# LED_Indicator.net
KiCad netlist of a schematic drawn in Altium Designer
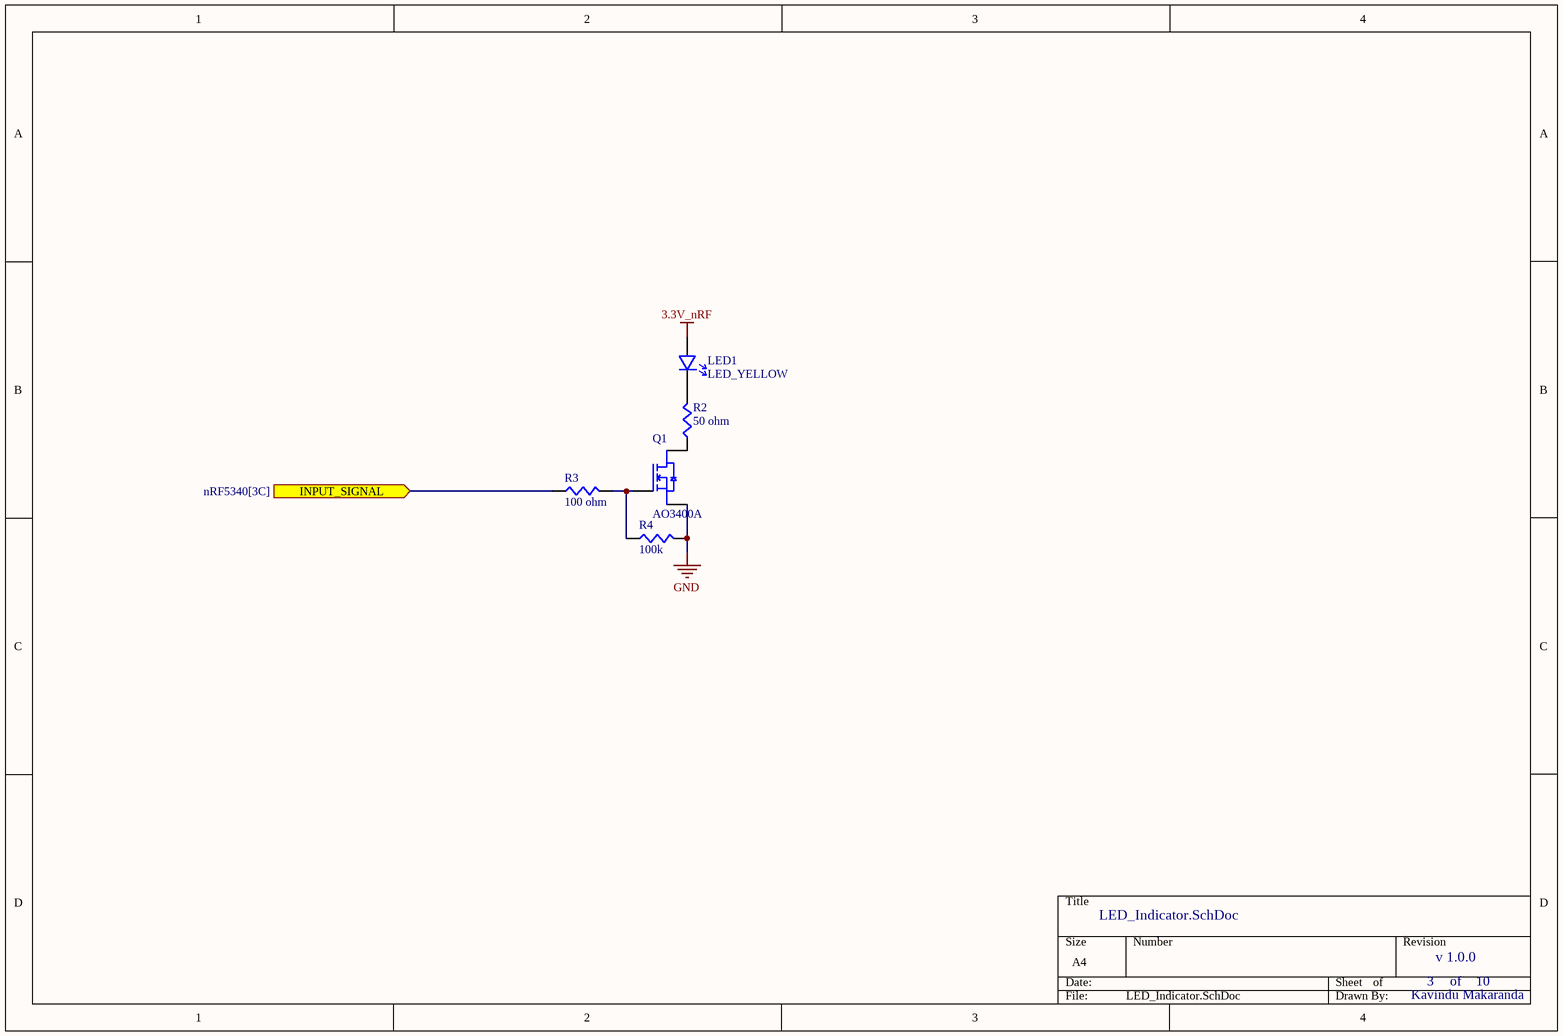
[diagram p0: LED_Indicator.SchDoc]

(export (version "E")
  (design (tool "Eeschema 10.0.6"))
  (components
    (comp (ref "LED1")
      (value "LED_YELLOW")
      (footprint "LED_0805_127P120X200-2N")
      (libsource (lib "Schlib1") (part "LED0805_YELLOW"))
    )
    (comp (ref "Q1")
      (value "AO3400A")
      (footprint "SOT23_P240X110-3N")
      (libsource (lib "Schlib1") (part "SOT_23_AO3400A"))
    )
    (comp (ref "R2")
      (value "50 ohm")
      (footprint "RECS0603X45N")
      (libsource (lib "Schlib1") (part "RESC0603_50_THIN"))
    )
    (comp (ref "R3")
      (value "100 ohm")
      (footprint "RECS0603X45N")
      (libsource (lib "Schlib1") (part "RESC0603_100_THIN"))
    )
    (comp (ref "R4")
      (value "100k")
      (footprint "RECS0603X45N")
      (libsource (lib "Schlib1") (part "RESC0603_100K_THIN"))
    )
  )
  (nets
    (net (code "1") (name "/INPUT_SIGNAL") (class "Default")
      (node (ref "R3") (pin "1") (pinfunction "1_1") (pintype "passive"))
    )
    (net (code "2") (name "3.3V_nRF") (class "Default")
      (node (ref "LED1") (pin "2") (pinfunction "+_2") (pintype "passive"))
    )
    (net (code "3") (name "GND") (class "Default")
      (node (ref "Q1") (pin "2") (pinfunction "SOURCE_2") (pintype "passive"))
      (node (ref "R4") (pin "2") (pinfunction "2_2") (pintype "passive"))
    )
    (net (code "4") (name "Net-(LED1--)") (class "Default")
      (node (ref "LED1") (pin "1") (pinfunction "-_1") (pintype "passive"))
      (node (ref "R2") (pin "2") (pinfunction "2_2") (pintype "passive"))
    )
    (net (code "5") (name "Net-(Q1-DRAIN)") (class "Default")
      (node (ref "Q1") (pin "3") (pinfunction "DRAIN_3") (pintype "passive"))
      (node (ref "R2") (pin "1") (pinfunction "1_1") (pintype "passive"))
    )
    (net (code "6") (name "Net-(Q1-GATE)") (class "Default")
      (node (ref "Q1") (pin "1") (pinfunction "GATE_1") (pintype "passive"))
      (node (ref "R3") (pin "2") (pinfunction "2_2") (pintype "passive"))
      (node (ref "R4") (pin "1") (pinfunction "1_1") (pintype "passive"))
    )
  )
)
